# QuadController.net
KiCad netlist of a schematic drawn in EAGLE
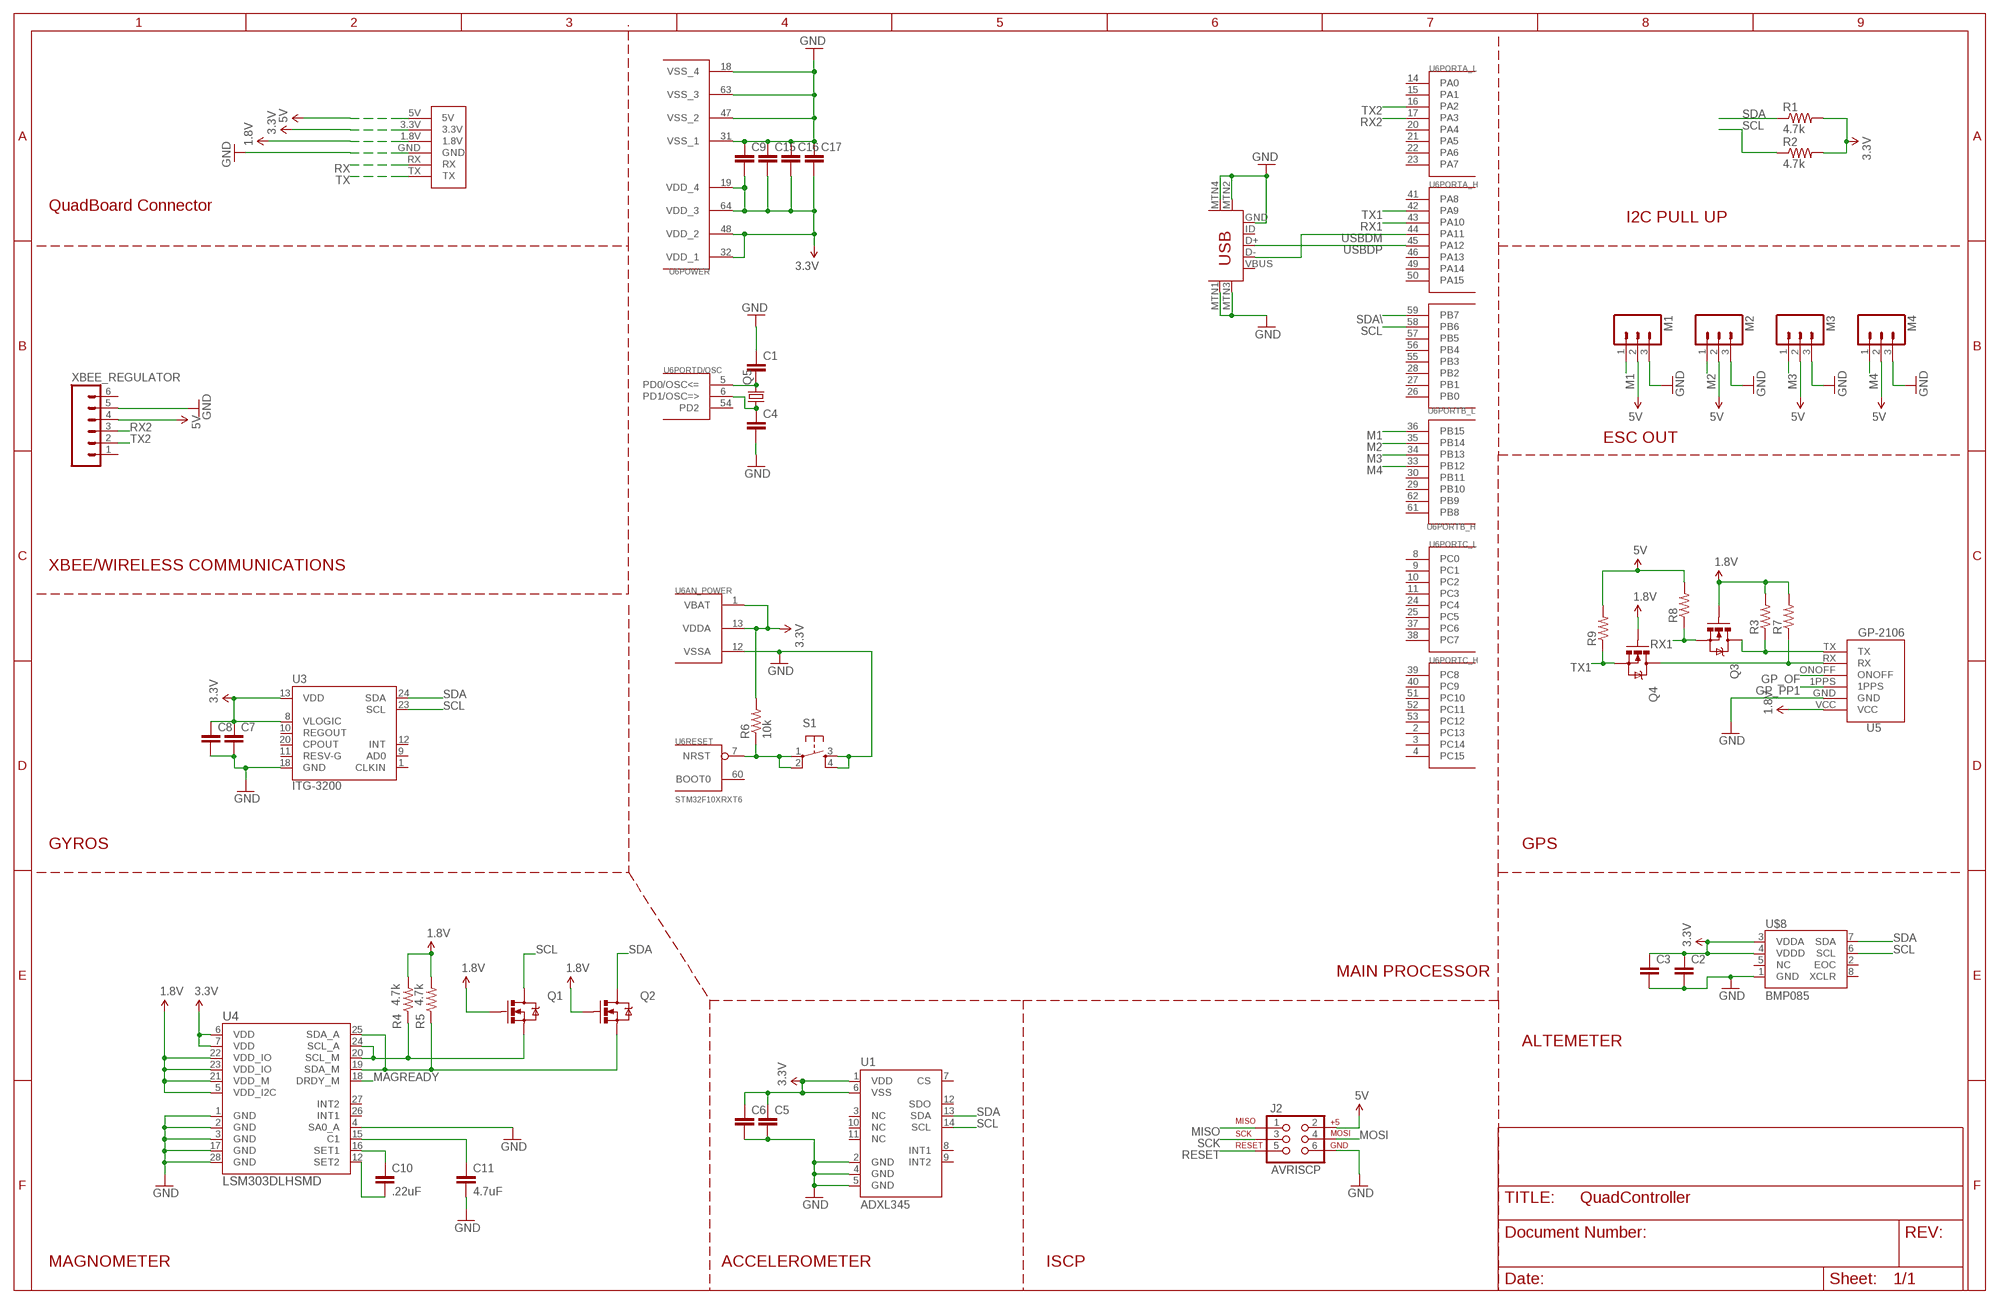
[diagram p0: schematic, sheet 1]

(export (version "E")
  (design (tool "Eeschema 10.0.6"))
  (components
    (comp (ref "C1")
      (value "CAP0805")
      (footprint "eagle-import:0805")
      (libsource (lib "eagle-import") (part "CAP0805"))
    )
    (comp (ref "C2")
      (value "CAP0805")
      (footprint "eagle-import:0805")
      (libsource (lib "eagle-import") (part "CAP0805"))
    )
    (comp (ref "C3")
      (value "CAP0805")
      (footprint "eagle-import:0805")
      (libsource (lib "eagle-import") (part "CAP0805"))
    )
    (comp (ref "C4")
      (value "CAP0805")
      (footprint "eagle-import:0805")
      (libsource (lib "eagle-import") (part "CAP0805"))
    )
    (comp (ref "C5")
      (value "CAP0805")
      (footprint "eagle-import:0805")
      (libsource (lib "eagle-import") (part "CAP0805"))
    )
    (comp (ref "C6")
      (value "CAP0805")
      (footprint "eagle-import:0805")
      (libsource (lib "eagle-import") (part "CAP0805"))
    )
    (comp (ref "C7")
      (value "CAP0805")
      (footprint "eagle-import:0805")
      (libsource (lib "eagle-import") (part "CAP0805"))
    )
    (comp (ref "C8")
      (value "CAP0805")
      (footprint "eagle-import:0805")
      (libsource (lib "eagle-import") (part "CAP0805"))
    )
    (comp (ref "C9")
      (value "CAP0805")
      (footprint "eagle-import:0805")
      (libsource (lib "eagle-import") (part "CAP0805"))
    )
    (comp (ref "C10")
      (value ".22uF")
      (footprint "eagle-import:0805")
      (libsource (lib "eagle-import") (part "CAP0805"))
    )
    (comp (ref "C11")
      (value "4.7uF")
      (footprint "eagle-import:0805")
      (libsource (lib "eagle-import") (part "CAP0805"))
    )
    (comp (ref "C15")
      (value "CAP0805")
      (footprint "eagle-import:0805")
      (libsource (lib "eagle-import") (part "CAP0805"))
    )
    (comp (ref "C16")
      (value "CAP0805")
      (footprint "eagle-import:0805")
      (libsource (lib "eagle-import") (part "CAP0805"))
    )
    (comp (ref "C17")
      (value "CAP0805")
      (footprint "eagle-import:0805")
      (libsource (lib "eagle-import") (part "CAP0805"))
    )
    (comp (ref "J2")
      (value "AVRISCP")
      (footprint "eagle-import:2X3")
      (libsource (lib "eagle-import") (part "AVR_SPI_PRG_6PTH"))
    )
    (comp (ref "M1")
      (value "M03PTH")
      (footprint "eagle-import:1X03")
      (libsource (lib "eagle-import") (part "M03PTH"))
    )
    (comp (ref "M2")
      (value "M03PTH")
      (footprint "eagle-import:1X03")
      (libsource (lib "eagle-import") (part "M03PTH"))
    )
    (comp (ref "M3")
      (value "M03PTH")
      (footprint "eagle-import:1X03")
      (libsource (lib "eagle-import") (part "M03PTH"))
    )
    (comp (ref "M4")
      (value "M03PTH")
      (footprint "eagle-import:1X03")
      (libsource (lib "eagle-import") (part "M03PTH"))
    )
    (comp (ref "Q1")
      (value "MOSFET-NCHANNELSMD")
      (footprint "eagle-import:SOT23-3")
      (libsource (lib "eagle-import") (part "MOSFET-NCHANNELSMD"))
    )
    (comp (ref "Q2")
      (value "MOSFET-NCHANNELSMD")
      (footprint "eagle-import:SOT23-3")
      (libsource (lib "eagle-import") (part "MOSFET-NCHANNELSMD"))
    )
    (comp (ref "Q3")
      (value "MOSFET-NCHANNELSMD")
      (footprint "eagle-import:SOT23-3")
      (libsource (lib "eagle-import") (part "MOSFET-NCHANNELSMD"))
    )
    (comp (ref "Q4")
      (value "MOSFET-NCHANNELSMD")
      (footprint "eagle-import:SOT23-3")
      (libsource (lib "eagle-import") (part "MOSFET-NCHANNELSMD"))
    )
    (comp (ref "Q5")
      (value "CRYSTALHC49UP")
      (footprint "eagle-import:HC49UP")
      (libsource (lib "eagle-import") (part "CRYSTALHC49UP"))
    )
    (comp (ref "QB1")
      (value "QUADBOARD")
      (footprint "eagle-import:QUADBOARD")
      (libsource (lib "eagle-import") (part "QUADBOARD"))
    )
    (comp (ref "R1")
      (value "4.7k")
      (footprint "eagle-import:0805")
      (libsource (lib "eagle-import") (part "RESISTOR0805-RES"))
    )
    (comp (ref "R2")
      (value "4.7k")
      (footprint "eagle-import:0805")
      (libsource (lib "eagle-import") (part "RESISTOR0805-RES"))
    )
    (comp (ref "R3")
      (value "RESISTOR0805-RES")
      (footprint "eagle-import:0805")
      (libsource (lib "eagle-import") (part "RESISTOR0805-RES"))
    )
    (comp (ref "R4")
      (value "4.7k")
      (footprint "eagle-import:0805")
      (libsource (lib "eagle-import") (part "RESISTOR0805-RES"))
    )
    (comp (ref "R5")
      (value "4.7k")
      (footprint "eagle-import:0805")
      (libsource (lib "eagle-import") (part "RESISTOR0805-RES"))
    )
    (comp (ref "R6")
      (value "10k")
      (footprint "eagle-import:0805")
      (libsource (lib "eagle-import") (part "RESISTOR0805-RES"))
    )
    (comp (ref "R7")
      (value "RESISTOR0805-RES")
      (footprint "eagle-import:0805")
      (libsource (lib "eagle-import") (part "RESISTOR0805-RES"))
    )
    (comp (ref "R8")
      (value "RESISTOR0805-RES")
      (footprint "eagle-import:0805")
      (libsource (lib "eagle-import") (part "RESISTOR0805-RES"))
    )
    (comp (ref "R9")
      (value "RESISTOR0805-RES")
      (footprint "eagle-import:0805")
      (libsource (lib "eagle-import") (part "RESISTOR0805-RES"))
    )
    (comp (ref "S1")
      (value "TAC_SWITCHSMD")
      (footprint "eagle-import:TACTILE_SWITCH_SMD")
      (libsource (lib "eagle-import") (part "TAC_SWITCHSMD"))
    )
    (comp (ref "U$1")
      (value "USB-MINIB-5PIN")
      (footprint "eagle-import:USB-MINIB")
      (libsource (lib "eagle-import") (part "USB-MINIB-5PIN"))
    )
    (comp (ref "U$8")
      (value "BMP085")
      (footprint "eagle-import:BMP085")
      (libsource (lib "eagle-import") (part "BMP085"))
    )
    (comp (ref "U1")
      (value "ADXL345")
      (footprint "eagle-import:LGA14")
      (libsource (lib "eagle-import") (part "ADXL345"))
    )
    (comp (ref "U3")
      (value "ITG-3200")
      (footprint "eagle-import:QFN-24")
      (libsource (lib "eagle-import") (part "ITG-3200"))
    )
    (comp (ref "U4")
      (value "LSM303DLHSMD")
      (footprint "eagle-import:LGA28-5X5")
      (libsource (lib "eagle-import") (part "LSM303DLHSMD"))
    )
    (comp (ref "U5")
      (value "GP-2106")
      (footprint "eagle-import:GP-2106")
      (libsource (lib "eagle-import") (part "GP-2106"))
    )
    (comp (ref "U6")
      (value "STM32F10XRXT6")
      (footprint "eagle-import:TQFP64")
      (libsource (lib "eagle-import") (part "STM32F10XRXT6"))
    )
    (comp (ref "XBEE_REGULATOR")
      (value "M06SIP")
      (footprint "eagle-import:1X06")
      (libsource (lib "eagle-import") (part "M06SIP"))
    )
  )
  (nets
    (net (code "1") (name "/GP_OF") (class "Default")
      (node (ref "U5") (pin "ONOFF") (pinfunction "ONOFF_ONOFF") (pintype "bidirectional"))
    )
    (net (code "2") (name "/GP_PP1") (class "Default")
      (node (ref "U5") (pin "1PPS") (pinfunction "1PPS_1PPS") (pintype "bidirectional"))
    )
    (net (code "3") (name "/M1") (class "Default")
      (node (ref "M1") (pin "1") (pinfunction "1_1") (pintype "passive"))
      (node (ref "U6") (pin "36") (pinfunction "PB15_36") (pintype "bidirectional"))
    )
    (net (code "4") (name "/M2") (class "Default")
      (node (ref "M2") (pin "1") (pinfunction "1_1") (pintype "passive"))
      (node (ref "U6") (pin "35") (pinfunction "PB14_35") (pintype "bidirectional"))
    )
    (net (code "5") (name "/M3") (class "Default")
      (node (ref "M3") (pin "1") (pinfunction "1_1") (pintype "passive"))
      (node (ref "U6") (pin "34") (pinfunction "PB13_34") (pintype "bidirectional"))
    )
    (net (code "6") (name "/M4") (class "Default")
      (node (ref "M4") (pin "1") (pinfunction "1_1") (pintype "passive"))
      (node (ref "U6") (pin "33") (pinfunction "PB12_33") (pintype "bidirectional"))
    )
    (net (code "7") (name "/MAGREADY") (class "Default")
      (node (ref "U4") (pin "18") (pinfunction "DRDY_M_18") (pintype "bidirectional"))
    )
    (net (code "8") (name "/MISO") (class "Default")
      (node (ref "J2") (pin "1") (pinfunction "1_1") (pintype "passive"))
    )
    (net (code "9") (name "/MOSI") (class "Default")
      (node (ref "J2") (pin "4") (pinfunction "4_4") (pintype "passive"))
    )
    (net (code "10") (name "/RESET") (class "Default")
      (node (ref "J2") (pin "5") (pinfunction "5_5") (pintype "passive"))
    )
    (net (code "11") (name "/RX") (class "Default")
      (node (ref "QB1") (pin "RX") (pinfunction "RX_RX") (pintype "bidirectional"))
    )
    (net (code "12") (name "/RX1") (class "Default")
      (node (ref "Q3") (pin "2") (pinfunction "S_2") (pintype "passive"))
      (node (ref "R8") (pin "1") (pinfunction "1_1") (pintype "passive"))
      (node (ref "U6") (pin "43") (pinfunction "PA10_43") (pintype "bidirectional"))
    )
    (net (code "13") (name "/RX2") (class "Default")
      (node (ref "U6") (pin "17") (pinfunction "PA3_17") (pintype "bidirectional"))
      (node (ref "XBEE_REGULATOR") (pin "3") (pinfunction "3_3") (pintype "passive"))
    )
    (net (code "14") (name "/SCK") (class "Default")
      (node (ref "J2") (pin "3") (pinfunction "3_3") (pintype "passive"))
    )
    (net (code "15") (name "/SCL") (class "Default")
      (node (ref "Q1") (pin "3") (pinfunction "D_3") (pintype "passive"))
      (node (ref "R2") (pin "1") (pinfunction "1_1") (pintype "passive"))
      (node (ref "U$8") (pin "6") (pinfunction "SCL_6") (pintype "input"))
      (node (ref "U1") (pin "14") (pinfunction "SCL_14") (pintype "bidirectional"))
      (node (ref "U3") (pin "23") (pinfunction "SCL_23") (pintype "bidirectional"))
      (node (ref "U6") (pin "58") (pinfunction "PB6_58") (pintype "bidirectional"))
    )
    (net (code "16") (name "/SDA") (class "Default")
      (node (ref "Q2") (pin "3") (pinfunction "D_3") (pintype "passive"))
      (node (ref "R1") (pin "1") (pinfunction "1_1") (pintype "passive"))
      (node (ref "U$8") (pin "7") (pinfunction "SDA_7") (pintype "bidirectional"))
      (node (ref "U1") (pin "13") (pinfunction "SDA_13") (pintype "bidirectional"))
      (node (ref "U3") (pin "24") (pinfunction "SDA_24") (pintype "bidirectional"))
    )
    (net (code "17") (name "/SDA\\") (class "Default")
      (node (ref "U6") (pin "59") (pinfunction "PB7_59") (pintype "bidirectional"))
    )
    (net (code "18") (name "/TX") (class "Default")
      (node (ref "QB1") (pin "TX") (pinfunction "TX_TX") (pintype "bidirectional"))
    )
    (net (code "19") (name "/TX1") (class "Default")
      (node (ref "Q4") (pin "2") (pinfunction "S_2") (pintype "passive"))
      (node (ref "R9") (pin "1") (pinfunction "1_1") (pintype "passive"))
      (node (ref "U6") (pin "42") (pinfunction "PA9_42") (pintype "bidirectional"))
    )
    (net (code "20") (name "/TX2") (class "Default")
      (node (ref "U6") (pin "16") (pinfunction "PA2_16") (pintype "bidirectional"))
      (node (ref "XBEE_REGULATOR") (pin "2") (pinfunction "2_2") (pintype "passive"))
    )
    (net (code "21") (name "/USBDM") (class "Default")
      (node (ref "U$1") (pin "D-") (pinfunction "D-_D-") (pintype "bidirectional"))
      (node (ref "U6") (pin "44") (pinfunction "PA11_44") (pintype "bidirectional"))
    )
    (net (code "22") (name "/USBDP") (class "Default")
      (node (ref "U$1") (pin "D+") (pinfunction "D+_D+") (pintype "bidirectional"))
      (node (ref "U6") (pin "45") (pinfunction "PA12_45") (pintype "bidirectional"))
    )
    (net (code "23") (name "1.8V") (class "Default")
      (node (ref "Q1") (pin "1") (pinfunction "G_1") (pintype "passive"))
      (node (ref "Q2") (pin "1") (pinfunction "G_1") (pintype "passive"))
      (node (ref "Q3") (pin "1") (pinfunction "G_1") (pintype "passive"))
      (node (ref "Q4") (pin "1") (pinfunction "G_1") (pintype "passive"))
      (node (ref "QB1") (pin "1.8V") (pinfunction "1.8V_1.8V") (pintype "bidirectional"))
      (node (ref "R3") (pin "2") (pinfunction "2_2") (pintype "passive"))
      (node (ref "R4") (pin "2") (pinfunction "2_2") (pintype "passive"))
      (node (ref "R5") (pin "2") (pinfunction "2_2") (pintype "passive"))
      (node (ref "R7") (pin "2") (pinfunction "2_2") (pintype "passive"))
      (node (ref "U4") (pin "21") (pinfunction "VDD_M_21") (pintype "bidirectional"))
      (node (ref "U4") (pin "22") (pinfunction "VDD_IO_22") (pintype "bidirectional"))
      (node (ref "U4") (pin "23") (pinfunction "VDD_IO_23") (pintype "bidirectional"))
      (node (ref "U4") (pin "5") (pinfunction "VDD_I2C_5") (pintype "bidirectional"))
      (node (ref "U5") (pin "VCC") (pinfunction "VCC_VCC") (pintype "bidirectional"))
    )
    (net (code "24") (name "3.3V") (class "Default")
      (node (ref "C15") (pin "2") (pinfunction "2_2") (pintype "passive"))
      (node (ref "C16") (pin "2") (pinfunction "2_2") (pintype "passive"))
      (node (ref "C17") (pin "2") (pinfunction "2_2") (pintype "passive"))
      (node (ref "C2") (pin "1") (pinfunction "1_1") (pintype "passive"))
      (node (ref "C3") (pin "1") (pinfunction "1_1") (pintype "passive"))
      (node (ref "C5") (pin "1") (pinfunction "1_1") (pintype "passive"))
      (node (ref "C6") (pin "1") (pinfunction "1_1") (pintype "passive"))
      (node (ref "C7") (pin "1") (pinfunction "1_1") (pintype "passive"))
      (node (ref "C8") (pin "1") (pinfunction "1_1") (pintype "passive"))
      (node (ref "C9") (pin "2") (pinfunction "2_2") (pintype "passive"))
      (node (ref "QB1") (pin "3.3V") (pinfunction "3.3V_3.3V") (pintype "bidirectional"))
      (node (ref "R1") (pin "2") (pinfunction "2_2") (pintype "passive"))
      (node (ref "R2") (pin "2") (pinfunction "2_2") (pintype "passive"))
      (node (ref "R6") (pin "2") (pinfunction "2_2") (pintype "passive"))
      (node (ref "U$8") (pin "3") (pinfunction "VDDA_3") (pintype "power_in"))
      (node (ref "U$8") (pin "4") (pinfunction "VDDD_4") (pintype "power_in"))
      (node (ref "U1") (pin "1") (pinfunction "VDD_1") (pintype "bidirectional"))
      (node (ref "U1") (pin "6") (pinfunction "VSS_6") (pintype "bidirectional"))
      (node (ref "U3") (pin "13") (pinfunction "VDD_13") (pintype "bidirectional"))
      (node (ref "U3") (pin "8") (pinfunction "VLOGIC_8") (pintype "bidirectional"))
      (node (ref "U4") (pin "6") (pinfunction "VDD_6") (pintype "bidirectional"))
      (node (ref "U4") (pin "7") (pinfunction "VDD_7") (pintype "bidirectional"))
      (node (ref "U6") (pin "1") (pinfunction "VBAT_1") (pintype "power_in"))
      (node (ref "U6") (pin "13") (pinfunction "VDDA_13") (pintype "power_in"))
      (node (ref "U6") (pin "19") (pinfunction "VDD_4_19") (pintype "power_in"))
      (node (ref "U6") (pin "32") (pinfunction "VDD_1_32") (pintype "power_in"))
      (node (ref "U6") (pin "48") (pinfunction "VDD_2_48") (pintype "power_in"))
      (node (ref "U6") (pin "64") (pinfunction "VDD_3_64") (pintype "power_in"))
    )
    (net (code "25") (name "5V") (class "Default")
      (node (ref "J2") (pin "2") (pinfunction "2_2") (pintype "passive"))
      (node (ref "M1") (pin "2") (pinfunction "2_2") (pintype "passive"))
      (node (ref "M2") (pin "2") (pinfunction "2_2") (pintype "passive"))
      (node (ref "M3") (pin "2") (pinfunction "2_2") (pintype "passive"))
      (node (ref "M4") (pin "2") (pinfunction "2_2") (pintype "passive"))
      (node (ref "QB1") (pin "5V") (pinfunction "5V_5V") (pintype "bidirectional"))
      (node (ref "R8") (pin "2") (pinfunction "2_2") (pintype "passive"))
      (node (ref "R9") (pin "2") (pinfunction "2_2") (pintype "passive"))
      (node (ref "XBEE_REGULATOR") (pin "4") (pinfunction "4_4") (pintype "passive"))
    )
    (net (code "26") (name "GND") (class "Default")
      (node (ref "C1") (pin "1") (pinfunction "1_1") (pintype "passive"))
      (node (ref "C11") (pin "2") (pinfunction "2_2") (pintype "passive"))
      (node (ref "C15") (pin "1") (pinfunction "1_1") (pintype "passive"))
      (node (ref "C16") (pin "1") (pinfunction "1_1") (pintype "passive"))
      (node (ref "C17") (pin "1") (pinfunction "1_1") (pintype "passive"))
      (node (ref "C2") (pin "2") (pinfunction "2_2") (pintype "passive"))
      (node (ref "C3") (pin "2") (pinfunction "2_2") (pintype "passive"))
      (node (ref "C4") (pin "2") (pinfunction "2_2") (pintype "passive"))
      (node (ref "C5") (pin "2") (pinfunction "2_2") (pintype "passive"))
      (node (ref "C6") (pin "2") (pinfunction "2_2") (pintype "passive"))
      (node (ref "C7") (pin "2") (pinfunction "2_2") (pintype "passive"))
      (node (ref "C8") (pin "2") (pinfunction "2_2") (pintype "passive"))
      (node (ref "C9") (pin "1") (pinfunction "1_1") (pintype "passive"))
      (node (ref "J2") (pin "6") (pinfunction "6_6") (pintype "passive"))
      (node (ref "M1") (pin "3") (pinfunction "3_3") (pintype "passive"))
      (node (ref "M2") (pin "3") (pinfunction "3_3") (pintype "passive"))
      (node (ref "M3") (pin "3") (pinfunction "3_3") (pintype "passive"))
      (node (ref "M4") (pin "3") (pinfunction "3_3") (pintype "passive"))
      (node (ref "QB1") (pin "GND") (pinfunction "GND_GND") (pintype "bidirectional"))
      (node (ref "S1") (pin "3") (pinfunction "3_3") (pintype "passive"))
      (node (ref "S1") (pin "4") (pinfunction "4_4") (pintype "passive"))
      (node (ref "U$1") (pin "GND") (pinfunction "GND_GND") (pintype "bidirectional"))
      (node (ref "U$1") (pin "MTN1") (pinfunction "MTN2_MTN1") (pintype "bidirectional"))
      (node (ref "U$1") (pin "MTN2") (pinfunction "MTN3_MTN2") (pintype "bidirectional"))
      (node (ref "U$1") (pin "MTN3") (pinfunction "MTN1_MTN3") (pintype "bidirectional"))
      (node (ref "U$1") (pin "MTN4") (pinfunction "MTN4_MTN4") (pintype "bidirectional"))
      (node (ref "U$8") (pin "1") (pinfunction "GND_1") (pintype "power_in"))
      (node (ref "U1") (pin "2") (pinfunction "GND_2") (pintype "bidirectional"))
      (node (ref "U1") (pin "4") (pinfunction "GND_4") (pintype "bidirectional"))
      (node (ref "U1") (pin "5") (pinfunction "GND_5") (pintype "bidirectional"))
      (node (ref "U3") (pin "18") (pinfunction "GND_18") (pintype "bidirectional"))
      (node (ref "U4") (pin "1") (pinfunction "GND_1") (pintype "bidirectional"))
      (node (ref "U4") (pin "17") (pinfunction "GND_17") (pintype "bidirectional"))
      (node (ref "U4") (pin "2") (pinfunction "GND_2") (pintype "bidirectional"))
      (node (ref "U4") (pin "28") (pinfunction "GND_28") (pintype "bidirectional"))
      (node (ref "U4") (pin "3") (pinfunction "GND_3") (pintype "bidirectional"))
      (node (ref "U4") (pin "4") (pinfunction "SA0_A_4") (pintype "bidirectional"))
      (node (ref "U5") (pin "GND") (pinfunction "GND_GND") (pintype "bidirectional"))
      (node (ref "U6") (pin "12") (pinfunction "VSSA_12") (pintype "power_in"))
      (node (ref "U6") (pin "18") (pinfunction "VSS_4_18") (pintype "power_in"))
      (node (ref "U6") (pin "31") (pinfunction "VSS_1_31") (pintype "power_in"))
      (node (ref "U6") (pin "47") (pinfunction "VSS_2_47") (pintype "power_in"))
      (node (ref "U6") (pin "63") (pinfunction "VSS_3_63") (pintype "power_in"))
      (node (ref "XBEE_REGULATOR") (pin "5") (pinfunction "5_5") (pintype "passive"))
    )
    (net (code "27") (name "Net-(Q1-S)") (class "Default")
      (node (ref "Q1") (pin "2") (pinfunction "S_2") (pintype "passive"))
      (node (ref "R4") (pin "1") (pinfunction "1_1") (pintype "passive"))
      (node (ref "U4") (pin "20") (pinfunction "SCL_M_20") (pintype "bidirectional"))
      (node (ref "U4") (pin "24") (pinfunction "SCL_A_24") (pintype "bidirectional"))
    )
    (net (code "28") (name "Net-(Q2-S)") (class "Default")
      (node (ref "Q2") (pin "2") (pinfunction "S_2") (pintype "passive"))
      (node (ref "R5") (pin "1") (pinfunction "1_1") (pintype "passive"))
      (node (ref "U4") (pin "19") (pinfunction "SDA_M_19") (pintype "bidirectional"))
      (node (ref "U4") (pin "25") (pinfunction "SDA_A_25") (pintype "bidirectional"))
    )
    (net (code "29") (name "Net-(Q3-D)") (class "Default")
      (node (ref "Q3") (pin "3") (pinfunction "D_3") (pintype "passive"))
      (node (ref "R3") (pin "1") (pinfunction "1_1") (pintype "passive"))
      (node (ref "U5") (pin "TX") (pinfunction "TX_TX") (pintype "bidirectional"))
    )
    (net (code "30") (name "Net-(Q4-D)") (class "Default")
      (node (ref "Q4") (pin "3") (pinfunction "D_3") (pintype "passive"))
      (node (ref "R7") (pin "1") (pinfunction "1_1") (pintype "passive"))
      (node (ref "U5") (pin "RX") (pinfunction "RX_RX") (pintype "bidirectional"))
    )
    (net (code "31") (name "Net-(U4-C1)") (class "Default")
      (node (ref "C11") (pin "1") (pinfunction "1_1") (pintype "passive"))
      (node (ref "U4") (pin "15") (pinfunction "C1_15") (pintype "bidirectional"))
    )
    (net (code "32") (name "Net-(U4-SET1)") (class "Default")
      (node (ref "C10") (pin "1") (pinfunction "1_1") (pintype "passive"))
      (node (ref "U4") (pin "16") (pinfunction "SET1_16") (pintype "bidirectional"))
    )
    (net (code "33") (name "Net-(U4-SET2)") (class "Default")
      (node (ref "C10") (pin "2") (pinfunction "2_2") (pintype "passive"))
      (node (ref "U4") (pin "12") (pinfunction "SET2_12") (pintype "bidirectional"))
    )
    (net (code "34") (name "Net-(U6H-PD0{slash}OSC<=)") (class "Default")
      (node (ref "C1") (pin "2") (pinfunction "2_2") (pintype "passive"))
      (node (ref "Q5") (pin "2") (pinfunction "2_2") (pintype "passive"))
      (node (ref "U6") (pin "5") (pinfunction "PD0/OSC<=_5") (pintype "bidirectional"))
    )
    (net (code "35") (name "Net-(U6H-PD1{slash}OSC=>)") (class "Default")
      (node (ref "C4") (pin "1") (pinfunction "1_1") (pintype "passive"))
      (node (ref "Q5") (pin "1") (pinfunction "1_1") (pintype "passive"))
      (node (ref "U6") (pin "6") (pinfunction "PD1/OSC=>_6") (pintype "bidirectional"))
    )
    (net (code "36") (name "Net-(U6J-NRST)") (class "Default")
      (node (ref "R6") (pin "1") (pinfunction "1_1") (pintype "passive"))
      (node (ref "S1") (pin "1") (pinfunction "1_1") (pintype "passive"))
      (node (ref "S1") (pin "2") (pinfunction "2_2") (pintype "passive"))
      (node (ref "U6") (pin "7") (pinfunction "NRST_7") (pintype "input"))
    )
    (net (code "37") (name "unconnected-(U$1-PadID)") (class "Default")
      (node (ref "U$1") (pin "ID") (pinfunction "ID_ID") (pintype "bidirectional"))
    )
    (net (code "38") (name "unconnected-(U$1-PadVBUS)") (class "Default")
      (node (ref "U$1") (pin "VBUS") (pinfunction "VBUS_VBUS") (pintype "bidirectional"))
    )
    (net (code "39") (name "unconnected-(U$8-EOC-Pad2)") (class "Default")
      (node (ref "U$8") (pin "2") (pinfunction "EOC_2") (pintype "output"))
    )
    (net (code "40") (name "unconnected-(U$8-NC-Pad5)") (class "Default")
      (node (ref "U$8") (pin "5") (pinfunction "NC_5") (pintype "bidirectional"))
    )
    (net (code "41") (name "unconnected-(U$8-XCLR-Pad8)") (class "Default")
      (node (ref "U$8") (pin "8") (pinfunction "XCLR_8") (pintype "input"))
    )
    (net (code "42") (name "unconnected-(U1-CS-Pad7)") (class "Default")
      (node (ref "U1") (pin "7") (pinfunction "CS_7") (pintype "bidirectional"))
    )
    (net (code "43") (name "unconnected-(U1-INT1-Pad8)") (class "Default")
      (node (ref "U1") (pin "8") (pinfunction "INT1_8") (pintype "bidirectional"))
    )
    (net (code "44") (name "unconnected-(U1-INT2-Pad9)") (class "Default")
      (node (ref "U1") (pin "9") (pinfunction "INT2_9") (pintype "bidirectional"))
    )
    (net (code "45") (name "unconnected-(U1-NC-Pad3)") (class "Default")
      (node (ref "U1") (pin "3") (pinfunction "NC_3") (pintype "bidirectional"))
    )
    (net (code "46") (name "unconnected-(U1-NC-Pad10)") (class "Default")
      (node (ref "U1") (pin "10") (pinfunction "NC_10") (pintype "bidirectional"))
    )
    (net (code "47") (name "unconnected-(U1-NC-Pad11)") (class "Default")
      (node (ref "U1") (pin "11") (pinfunction "NC_11") (pintype "bidirectional"))
    )
    (net (code "48") (name "unconnected-(U1-SDO-Pad12)") (class "Default")
      (node (ref "U1") (pin "12") (pinfunction "SDO_12") (pintype "bidirectional"))
    )
    (net (code "49") (name "unconnected-(U3-AD0-Pad9)") (class "Default")
      (node (ref "U3") (pin "9") (pinfunction "AD0_9") (pintype "bidirectional"))
    )
    (net (code "50") (name "unconnected-(U3-CLKIN-Pad1)") (class "Default")
      (node (ref "U3") (pin "1") (pinfunction "CLKIN_1") (pintype "bidirectional"))
    )
    (net (code "51") (name "unconnected-(U3-CPOUT-Pad20)") (class "Default")
      (node (ref "U3") (pin "20") (pinfunction "CPOUT_20") (pintype "bidirectional"))
    )
    (net (code "52") (name "unconnected-(U3-INT-Pad12)") (class "Default")
      (node (ref "U3") (pin "12") (pinfunction "INT_12") (pintype "bidirectional"))
    )
    (net (code "53") (name "unconnected-(U3-REGOUT-Pad10)") (class "Default")
      (node (ref "U3") (pin "10") (pinfunction "REGOUT_10") (pintype "bidirectional"))
    )
    (net (code "54") (name "unconnected-(U3-RESV-G-Pad11)") (class "Default")
      (node (ref "U3") (pin "11") (pinfunction "RESV-G_11") (pintype "bidirectional"))
    )
    (net (code "55") (name "unconnected-(U4-INT1-Pad26)") (class "Default")
      (node (ref "U4") (pin "26") (pinfunction "INT1_26") (pintype "bidirectional"))
    )
    (net (code "56") (name "unconnected-(U4-INT2-Pad27)") (class "Default")
      (node (ref "U4") (pin "27") (pinfunction "INT2_27") (pintype "bidirectional"))
    )
    (net (code "57") (name "unconnected-(U6B-PA8-Pad41)") (class "Default")
      (node (ref "U6") (pin "41") (pinfunction "PA8_41") (pintype "bidirectional"))
    )
    (net (code "58") (name "unconnected-(U6B-PA13-Pad46)") (class "Default")
      (node (ref "U6") (pin "46") (pinfunction "PA13_46") (pintype "bidirectional"))
    )
    (net (code "59") (name "unconnected-(U6B-PA14-Pad49)") (class "Default")
      (node (ref "U6") (pin "49") (pinfunction "PA14_49") (pintype "bidirectional"))
    )
    (net (code "60") (name "unconnected-(U6B-PA15-Pad50)") (class "Default")
      (node (ref "U6") (pin "50") (pinfunction "PA15_50") (pintype "bidirectional"))
    )
    (net (code "61") (name "unconnected-(U6C-PA0-Pad14)") (class "Default")
      (node (ref "U6") (pin "14") (pinfunction "PA0_14") (pintype "bidirectional"))
    )
    (net (code "62") (name "unconnected-(U6C-PA1-Pad15)") (class "Default")
      (node (ref "U6") (pin "15") (pinfunction "PA1_15") (pintype "bidirectional"))
    )
    (net (code "63") (name "unconnected-(U6C-PA4-Pad20)") (class "Default")
      (node (ref "U6") (pin "20") (pinfunction "PA4_20") (pintype "bidirectional"))
    )
    (net (code "64") (name "unconnected-(U6C-PA5-Pad21)") (class "Default")
      (node (ref "U6") (pin "21") (pinfunction "PA5_21") (pintype "bidirectional"))
    )
    (net (code "65") (name "unconnected-(U6C-PA6-Pad22)") (class "Default")
      (node (ref "U6") (pin "22") (pinfunction "PA6_22") (pintype "bidirectional"))
    )
    (net (code "66") (name "unconnected-(U6C-PA7-Pad23)") (class "Default")
      (node (ref "U6") (pin "23") (pinfunction "PA7_23") (pintype "bidirectional"))
    )
    (net (code "67") (name "unconnected-(U6D-PB8-Pad61)") (class "Default")
      (node (ref "U6") (pin "61") (pinfunction "PB8_61") (pintype "bidirectional"))
    )
    (net (code "68") (name "unconnected-(U6D-PB9-Pad62)") (class "Default")
      (node (ref "U6") (pin "62") (pinfunction "PB9_62") (pintype "bidirectional"))
    )
    (net (code "69") (name "unconnected-(U6D-PB10-Pad29)") (class "Default")
      (node (ref "U6") (pin "29") (pinfunction "PB10_29") (pintype "bidirectional"))
    )
    (net (code "70") (name "unconnected-(U6D-PB11-Pad30)") (class "Default")
      (node (ref "U6") (pin "30") (pinfunction "PB11_30") (pintype "bidirectional"))
    )
    (net (code "71") (name "unconnected-(U6E-PB0-Pad26)") (class "Default")
      (node (ref "U6") (pin "26") (pinfunction "PB0_26") (pintype "bidirectional"))
    )
    (net (code "72") (name "unconnected-(U6E-PB1-Pad27)") (class "Default")
      (node (ref "U6") (pin "27") (pinfunction "PB1_27") (pintype "bidirectional"))
    )
    (net (code "73") (name "unconnected-(U6E-PB2-Pad28)") (class "Default")
      (node (ref "U6") (pin "28") (pinfunction "PB2_28") (pintype "bidirectional"))
    )
    (net (code "74") (name "unconnected-(U6E-PB3-Pad55)") (class "Default")
      (node (ref "U6") (pin "55") (pinfunction "PB3_55") (pintype "bidirectional"))
    )
    (net (code "75") (name "unconnected-(U6E-PB4-Pad56)") (class "Default")
      (node (ref "U6") (pin "56") (pinfunction "PB4_56") (pintype "bidirectional"))
    )
    (net (code "76") (name "unconnected-(U6E-PB5-Pad57)") (class "Default")
      (node (ref "U6") (pin "57") (pinfunction "PB5_57") (pintype "bidirectional"))
    )
    (net (code "77") (name "unconnected-(U6F-PC8-Pad39)") (class "Default")
      (node (ref "U6") (pin "39") (pinfunction "PC8_39") (pintype "bidirectional"))
    )
    (net (code "78") (name "unconnected-(U6F-PC9-Pad40)") (class "Default")
      (node (ref "U6") (pin "40") (pinfunction "PC9_40") (pintype "bidirectional"))
    )
    (net (code "79") (name "unconnected-(U6F-PC10-Pad51)") (class "Default")
      (node (ref "U6") (pin "51") (pinfunction "PC10_51") (pintype "bidirectional"))
    )
    (net (code "80") (name "unconnected-(U6F-PC11-Pad52)") (class "Default")
      (node (ref "U6") (pin "52") (pinfunction "PC11_52") (pintype "bidirectional"))
    )
    (net (code "81") (name "unconnected-(U6F-PC12-Pad53)") (class "Default")
      (node (ref "U6") (pin "53") (pinfunction "PC12_53") (pintype "bidirectional"))
    )
    (net (code "82") (name "unconnected-(U6F-PC13-Pad2)") (class "Default")
      (node (ref "U6") (pin "2") (pinfunction "PC13_2") (pintype "bidirectional"))
    )
    (net (code "83") (name "unconnected-(U6F-PC14-Pad3)") (class "Default")
      (node (ref "U6") (pin "3") (pinfunction "PC14_3") (pintype "bidirectional"))
    )
    (net (code "84") (name "unconnected-(U6F-PC15-Pad4)") (class "Default")
      (node (ref "U6") (pin "4") (pinfunction "PC15_4") (pintype "bidirectional"))
    )
    (net (code "85") (name "unconnected-(U6G-PC0-Pad8)") (class "Default")
      (node (ref "U6") (pin "8") (pinfunction "PC0_8") (pintype "bidirectional"))
    )
    (net (code "86") (name "unconnected-(U6G-PC1-Pad9)") (class "Default")
      (node (ref "U6") (pin "9") (pinfunction "PC1_9") (pintype "bidirectional"))
    )
    (net (code "87") (name "unconnected-(U6G-PC2-Pad10)") (class "Default")
      (node (ref "U6") (pin "10") (pinfunction "PC2_10") (pintype "bidirectional"))
    )
    (net (code "88") (name "unconnected-(U6G-PC3-Pad11)") (class "Default")
      (node (ref "U6") (pin "11") (pinfunction "PC3_11") (pintype "bidirectional"))
    )
    (net (code "89") (name "unconnected-(U6G-PC4-Pad24)") (class "Default")
      (node (ref "U6") (pin "24") (pinfunction "PC4_24") (pintype "bidirectional"))
    )
    (net (code "90") (name "unconnected-(U6G-PC5-Pad25)") (class "Default")
      (node (ref "U6") (pin "25") (pinfunction "PC5_25") (pintype "bidirectional"))
    )
    (net (code "91") (name "unconnected-(U6G-PC6-Pad37)") (class "Default")
      (node (ref "U6") (pin "37") (pinfunction "PC6_37") (pintype "bidirectional"))
    )
    (net (code "92") (name "unconnected-(U6G-PC7-Pad38)") (class "Default")
      (node (ref "U6") (pin "38") (pinfunction "PC7_38") (pintype "bidirectional"))
    )
    (net (code "93") (name "unconnected-(U6H-PD2-Pad54)") (class "Default")
      (node (ref "U6") (pin "54") (pinfunction "PD2_54") (pintype "bidirectional"))
    )
    (net (code "94") (name "unconnected-(U6J-BOOT0-Pad60)") (class "Default")
      (node (ref "U6") (pin "60") (pinfunction "BOOT0_60") (pintype "input"))
    )
    (net (code "95") (name "unconnected-(XBEE_REGULATOR-Pad1)") (class "Default")
      (node (ref "XBEE_REGULATOR") (pin "1") (pinfunction "1_1") (pintype "passive"))
    )
    (net (code "96") (name "unconnected-(XBEE_REGULATOR-Pad6)") (class "Default")
      (node (ref "XBEE_REGULATOR") (pin "6") (pinfunction "6_6") (pintype "passive"))
    )
  )
)
